# right.net
KiCad netlist of a schematic drawn in Altium Designer
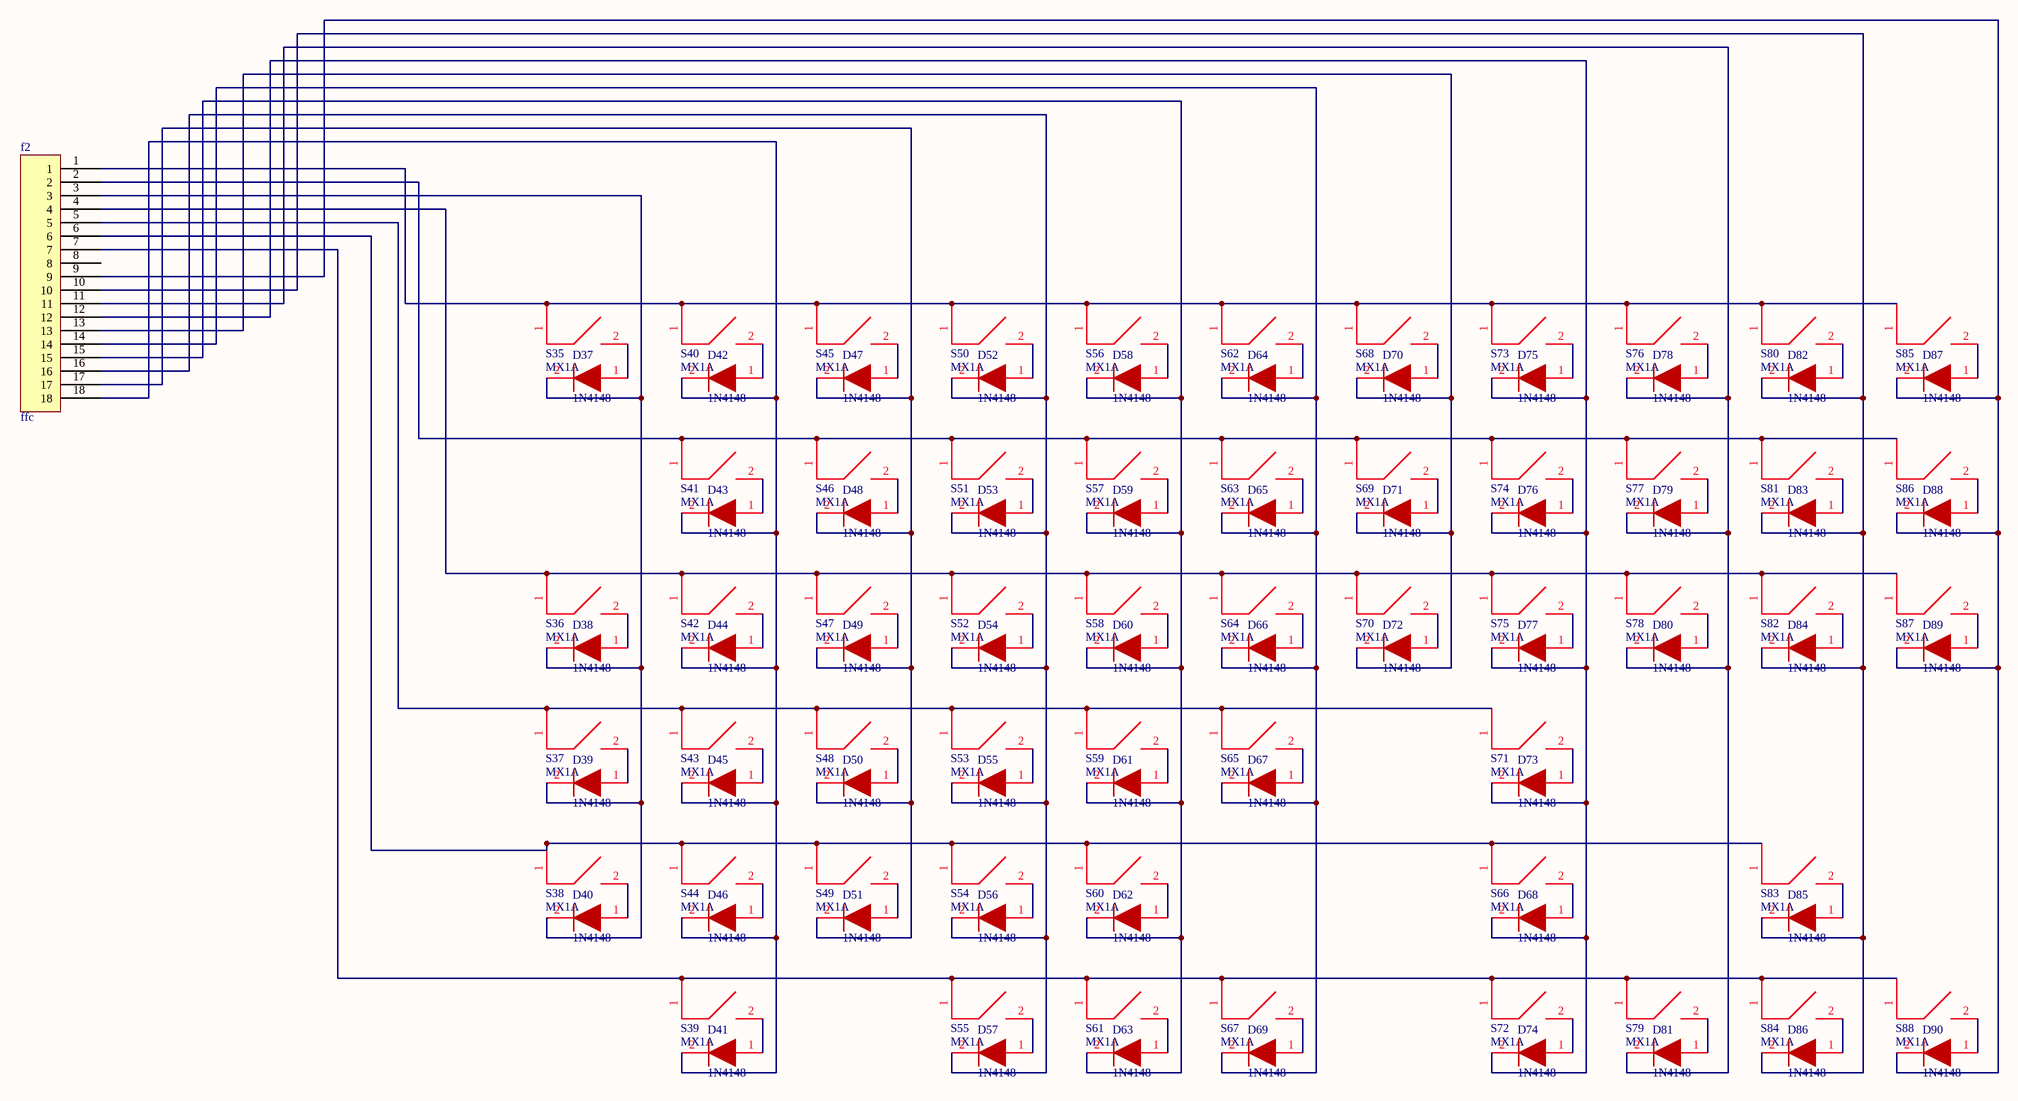
[diagram p0: right.SchDoc]

(export (version "E")
  (design (tool "Eeschema 10.0.6"))
  (components
    (comp (ref "D37")
      (value "1N4148")
      (footprint "SOD323")
      (description "二极管")
      (libsource (lib "keyboard") (part "1N4148"))
    )
    (comp (ref "D38")
      (value "1N4148")
      (footprint "SOD323")
      (description "二极管")
      (libsource (lib "keyboard") (part "1N4148"))
    )
    (comp (ref "D39")
      (value "1N4148")
      (footprint "SOD323")
      (description "二极管")
      (libsource (lib "keyboard") (part "1N4148"))
    )
    (comp (ref "D40")
      (value "1N4148")
      (footprint "SOD323")
      (description "二极管")
      (libsource (lib "keyboard") (part "1N4148"))
    )
    (comp (ref "D41")
      (value "1N4148")
      (footprint "SOD323")
      (description "二极管")
      (libsource (lib "keyboard") (part "1N4148"))
    )
    (comp (ref "D42")
      (value "1N4148")
      (footprint "SOD323")
      (description "二极管")
      (libsource (lib "keyboard") (part "1N4148"))
    )
    (comp (ref "D43")
      (value "1N4148")
      (footprint "SOD323")
      (description "二极管")
      (libsource (lib "keyboard") (part "1N4148"))
    )
    (comp (ref "D44")
      (value "1N4148")
      (footprint "SOD323")
      (description "二极管")
      (libsource (lib "keyboard") (part "1N4148"))
    )
    (comp (ref "D45")
      (value "1N4148")
      (footprint "SOD323")
      (description "二极管")
      (libsource (lib "keyboard") (part "1N4148"))
    )
    (comp (ref "D46")
      (value "1N4148")
      (footprint "SOD323")
      (description "二极管")
      (libsource (lib "keyboard") (part "1N4148"))
    )
    (comp (ref "D47")
      (value "1N4148")
      (footprint "SOD323")
      (description "二极管")
      (libsource (lib "keyboard") (part "1N4148"))
    )
    (comp (ref "D48")
      (value "1N4148")
      (footprint "SOD323")
      (description "二极管")
      (libsource (lib "keyboard") (part "1N4148"))
    )
    (comp (ref "D49")
      (value "1N4148")
      (footprint "SOD323")
      (description "二极管")
      (libsource (lib "keyboard") (part "1N4148"))
    )
    (comp (ref "D50")
      (value "1N4148")
      (footprint "SOD323")
      (description "二极管")
      (libsource (lib "keyboard") (part "1N4148"))
    )
    (comp (ref "D51")
      (value "1N4148")
      (footprint "SOD323")
      (description "二极管")
      (libsource (lib "keyboard") (part "1N4148"))
    )
    (comp (ref "D52")
      (value "1N4148")
      (footprint "SOD323")
      (description "二极管")
      (libsource (lib "keyboard") (part "1N4148"))
    )
    (comp (ref "D53")
      (value "1N4148")
      (footprint "SOD323")
      (description "二极管")
      (libsource (lib "keyboard") (part "1N4148"))
    )
    (comp (ref "D54")
      (value "1N4148")
      (footprint "SOD323")
      (description "二极管")
      (libsource (lib "keyboard") (part "1N4148"))
    )
    (comp (ref "D55")
      (value "1N4148")
      (footprint "SOD323")
      (description "二极管")
      (libsource (lib "keyboard") (part "1N4148"))
    )
    (comp (ref "D56")
      (value "1N4148")
      (footprint "SOD323")
      (description "二极管")
      (libsource (lib "keyboard") (part "1N4148"))
    )
    (comp (ref "D57")
      (value "1N4148")
      (footprint "SOD323")
      (description "二极管")
      (libsource (lib "keyboard") (part "1N4148"))
    )
    (comp (ref "D58")
      (value "1N4148")
      (footprint "SOD323")
      (description "二极管")
      (libsource (lib "keyboard") (part "1N4148"))
    )
    (comp (ref "D59")
      (value "1N4148")
      (footprint "SOD323")
      (description "二极管")
      (libsource (lib "keyboard") (part "1N4148"))
    )
    (comp (ref "D60")
      (value "1N4148")
      (footprint "SOD323")
      (description "二极管")
      (libsource (lib "keyboard") (part "1N4148"))
    )
    (comp (ref "D61")
      (value "1N4148")
      (footprint "SOD323")
      (description "二极管")
      (libsource (lib "keyboard") (part "1N4148"))
    )
    (comp (ref "D62")
      (value "1N4148")
      (footprint "SOD323")
      (description "二极管")
      (libsource (lib "keyboard") (part "1N4148"))
    )
    (comp (ref "D63")
      (value "1N4148")
      (footprint "SOD323")
      (description "二极管")
      (libsource (lib "keyboard") (part "1N4148"))
    )
    (comp (ref "D64")
      (value "1N4148")
      (footprint "SOD323")
      (description "二极管")
      (libsource (lib "keyboard") (part "1N4148"))
    )
    (comp (ref "D65")
      (value "1N4148")
      (footprint "SOD323")
      (description "二极管")
      (libsource (lib "keyboard") (part "1N4148"))
    )
    (comp (ref "D66")
      (value "1N4148")
      (footprint "SOD323")
      (description "二极管")
      (libsource (lib "keyboard") (part "1N4148"))
    )
    (comp (ref "D67")
      (value "1N4148")
      (footprint "SOD323")
      (description "二极管")
      (libsource (lib "keyboard") (part "1N4148"))
    )
    (comp (ref "D68")
      (value "1N4148")
      (footprint "SOD323")
      (description "二极管")
      (libsource (lib "keyboard") (part "1N4148"))
    )
    (comp (ref "D69")
      (value "1N4148")
      (footprint "SOD323")
      (description "二极管")
      (libsource (lib "keyboard") (part "1N4148"))
    )
    (comp (ref "D70")
      (value "1N4148")
      (footprint "SOD323")
      (description "二极管")
      (libsource (lib "keyboard") (part "1N4148"))
    )
    (comp (ref "D71")
      (value "1N4148")
      (footprint "SOD323")
      (description "二极管")
      (libsource (lib "keyboard") (part "1N4148"))
    )
    (comp (ref "D72")
      (value "1N4148")
      (footprint "SOD323")
      (description "二极管")
      (libsource (lib "keyboard") (part "1N4148"))
    )
    (comp (ref "D73")
      (value "1N4148")
      (footprint "SOD323")
      (description "二极管")
      (libsource (lib "keyboard") (part "1N4148"))
    )
    (comp (ref "D74")
      (value "1N4148")
      (footprint "SOD323")
      (description "二极管")
      (libsource (lib "keyboard") (part "1N4148"))
    )
    (comp (ref "D75")
      (value "1N4148")
      (footprint "SOD323")
      (description "二极管")
      (libsource (lib "keyboard") (part "1N4148"))
    )
    (comp (ref "D76")
      (value "1N4148")
      (footprint "SOD323")
      (description "二极管")
      (libsource (lib "keyboard") (part "1N4148"))
    )
    (comp (ref "D77")
      (value "1N4148")
      (footprint "SOD323")
      (description "二极管")
      (libsource (lib "keyboard") (part "1N4148"))
    )
    (comp (ref "D78")
      (value "1N4148")
      (footprint "SOD323")
      (description "二极管")
      (libsource (lib "keyboard") (part "1N4148"))
    )
    (comp (ref "D79")
      (value "1N4148")
      (footprint "SOD323")
      (description "二极管")
      (libsource (lib "keyboard") (part "1N4148"))
    )
    (comp (ref "D80")
      (value "1N4148")
      (footprint "SOD323")
      (description "二极管")
      (libsource (lib "keyboard") (part "1N4148"))
    )
    (comp (ref "D81")
      (value "1N4148")
      (footprint "SOD323")
      (description "二极管")
      (libsource (lib "keyboard") (part "1N4148"))
    )
    (comp (ref "D82")
      (value "1N4148")
      (footprint "SOD323")
      (description "二极管")
      (libsource (lib "keyboard") (part "1N4148"))
    )
    (comp (ref "D83")
      (value "1N4148")
      (footprint "SOD323")
      (description "二极管")
      (libsource (lib "keyboard") (part "1N4148"))
    )
    (comp (ref "D84")
      (value "1N4148")
      (footprint "SOD323")
      (description "二极管")
      (libsource (lib "keyboard") (part "1N4148"))
    )
    (comp (ref "D85")
      (value "1N4148")
      (footprint "SOD323")
      (description "二极管")
      (libsource (lib "keyboard") (part "1N4148"))
    )
    (comp (ref "D86")
      (value "1N4148")
      (footprint "SOD323")
      (description "二极管")
      (libsource (lib "keyboard") (part "1N4148"))
    )
    (comp (ref "D87")
      (value "1N4148")
      (footprint "SOD323")
      (description "二极管")
      (libsource (lib "keyboard") (part "1N4148"))
    )
    (comp (ref "D88")
      (value "1N4148")
      (footprint "SOD323")
      (description "二极管")
      (libsource (lib "keyboard") (part "1N4148"))
    )
    (comp (ref "D89")
      (value "1N4148")
      (footprint "SOD323")
      (description "二极管")
      (libsource (lib "keyboard") (part "1N4148"))
    )
    (comp (ref "D90")
      (value "1N4148")
      (footprint "SOD323")
      (description "二极管")
      (libsource (lib "keyboard") (part "1N4148"))
    )
    (comp (ref "f2") (value "ffc") (footprint "FFC") (libsource (lib "keyboard") (part "ffc")))
    (comp (ref "S35")
      (value "MX1A")
      (footprint "KEY")
      (description "按键")
      (libsource (lib "keyboard") (part "MX1A"))
    )
    (comp (ref "S36")
      (value "MX1A")
      (footprint "KEY")
      (description "按键")
      (libsource (lib "keyboard") (part "MX1A"))
    )
    (comp (ref "S37")
      (value "MX1A")
      (footprint "KEY")
      (description "按键")
      (libsource (lib "keyboard") (part "MX1A"))
    )
    (comp (ref "S38")
      (value "MX1A")
      (footprint "KEY")
      (description "按键")
      (libsource (lib "keyboard") (part "MX1A"))
    )
    (comp (ref "S39")
      (value "MX1A")
      (footprint "KEY")
      (description "按键")
      (libsource (lib "keyboard") (part "MX1A"))
    )
    (comp (ref "S40")
      (value "MX1A")
      (footprint "KEY")
      (description "按键")
      (libsource (lib "keyboard") (part "MX1A"))
    )
    (comp (ref "S41")
      (value "MX1A")
      (footprint "KEY")
      (description "按键")
      (libsource (lib "keyboard") (part "MX1A"))
    )
    (comp (ref "S42")
      (value "MX1A")
      (footprint "KEY")
      (description "按键")
      (libsource (lib "keyboard") (part "MX1A"))
    )
    (comp (ref "S43")
      (value "MX1A")
      (footprint "KEY")
      (description "按键")
      (libsource (lib "keyboard") (part "MX1A"))
    )
    (comp (ref "S44")
      (value "MX1A")
      (footprint "KEY")
      (description "按键")
      (libsource (lib "keyboard") (part "MX1A"))
    )
    (comp (ref "S45")
      (value "MX1A")
      (footprint "KEY")
      (description "按键")
      (libsource (lib "keyboard") (part "MX1A"))
    )
    (comp (ref "S46")
      (value "MX1A")
      (footprint "KEY")
      (description "按键")
      (libsource (lib "keyboard") (part "MX1A"))
    )
    (comp (ref "S47")
      (value "MX1A")
      (footprint "KEY")
      (description "按键")
      (libsource (lib "keyboard") (part "MX1A"))
    )
    (comp (ref "S48")
      (value "MX1A")
      (footprint "KEY")
      (description "按键")
      (libsource (lib "keyboard") (part "MX1A"))
    )
    (comp (ref "S49")
      (value "MX1A")
      (footprint "KEY")
      (description "按键")
      (libsource (lib "keyboard") (part "MX1A"))
    )
    (comp (ref "S50")
      (value "MX1A")
      (footprint "KEY")
      (description "按键")
      (libsource (lib "keyboard") (part "MX1A"))
    )
    (comp (ref "S51")
      (value "MX1A")
      (footprint "KEY")
      (description "按键")
      (libsource (lib "keyboard") (part "MX1A"))
    )
    (comp (ref "S52")
      (value "MX1A")
      (footprint "KEY")
      (description "按键")
      (libsource (lib "keyboard") (part "MX1A"))
    )
    (comp (ref "S53")
      (value "MX1A")
      (footprint "KEY")
      (description "按键")
      (libsource (lib "keyboard") (part "MX1A"))
    )
    (comp (ref "S54")
      (value "MX1A")
      (footprint "KEY")
      (description "按键")
      (libsource (lib "keyboard") (part "MX1A"))
    )
    (comp (ref "S55")
      (value "MX1A")
      (footprint "KEY")
      (description "按键")
      (libsource (lib "keyboard") (part "MX1A"))
    )
    (comp (ref "S56")
      (value "MX1A")
      (footprint "KEY")
      (description "按键")
      (libsource (lib "keyboard") (part "MX1A"))
    )
    (comp (ref "S57")
      (value "MX1A")
      (footprint "KEY")
      (description "按键")
      (libsource (lib "keyboard") (part "MX1A"))
    )
    (comp (ref "S58")
      (value "MX1A")
      (footprint "KEY")
      (description "按键")
      (libsource (lib "keyboard") (part "MX1A"))
    )
    (comp (ref "S59")
      (value "MX1A")
      (footprint "KEY")
      (description "按键")
      (libsource (lib "keyboard") (part "MX1A"))
    )
    (comp (ref "S60")
      (value "MX1A")
      (footprint "KEY")
      (description "按键")
      (libsource (lib "keyboard") (part "MX1A"))
    )
    (comp (ref "S61")
      (value "MX1A")
      (footprint "KEY")
      (description "按键")
      (libsource (lib "keyboard") (part "MX1A"))
    )
    (comp (ref "S62")
      (value "MX1A")
      (footprint "KEY")
      (description "按键")
      (libsource (lib "keyboard") (part "MX1A"))
    )
    (comp (ref "S63")
      (value "MX1A")
      (footprint "KEY")
      (description "按键")
      (libsource (lib "keyboard") (part "MX1A"))
    )
    (comp (ref "S64")
      (value "MX1A")
      (footprint "KEY")
      (description "按键")
      (libsource (lib "keyboard") (part "MX1A"))
    )
    (comp (ref "S65")
      (value "MX1A")
      (footprint "KEY")
      (description "按键")
      (libsource (lib "keyboard") (part "MX1A"))
    )
    (comp (ref "S66")
      (value "MX1A")
      (footprint "KEY")
      (description "按键")
      (libsource (lib "keyboard") (part "MX1A"))
    )
    (comp (ref "S67")
      (value "MX1A")
      (footprint "KEY")
      (description "按键")
      (libsource (lib "keyboard") (part "MX1A"))
    )
    (comp (ref "S68")
      (value "MX1A")
      (footprint "KEY")
      (description "按键")
      (libsource (lib "keyboard") (part "MX1A"))
    )
    (comp (ref "S69")
      (value "MX1A")
      (footprint "KEY")
      (description "按键")
      (libsource (lib "keyboard") (part "MX1A"))
    )
    (comp (ref "S70")
      (value "MX1A")
      (footprint "KEY")
      (description "按键")
      (libsource (lib "keyboard") (part "MX1A"))
    )
    (comp (ref "S71")
      (value "MX1A")
      (footprint "KEY")
      (description "按键")
      (libsource (lib "keyboard") (part "MX1A"))
    )
    (comp (ref "S72")
      (value "MX1A")
      (footprint "KEY")
      (description "按键")
      (libsource (lib "keyboard") (part "MX1A"))
    )
    (comp (ref "S73")
      (value "MX1A")
      (footprint "KEY")
      (description "按键")
      (libsource (lib "keyboard") (part "MX1A"))
    )
    (comp (ref "S74")
      (value "MX1A")
      (footprint "KEY")
      (description "按键")
      (libsource (lib "keyboard") (part "MX1A"))
    )
    (comp (ref "S75")
      (value "MX1A")
      (footprint "KEY")
      (description "按键")
      (libsource (lib "keyboard") (part "MX1A"))
    )
    (comp (ref "S76")
      (value "MX1A")
      (footprint "KEY")
      (description "按键")
      (libsource (lib "keyboard") (part "MX1A"))
    )
    (comp (ref "S77")
      (value "MX1A")
      (footprint "KEY")
      (description "按键")
      (libsource (lib "keyboard") (part "MX1A"))
    )
    (comp (ref "S78")
      (value "MX1A")
      (footprint "KEY")
      (description "按键")
      (libsource (lib "keyboard") (part "MX1A"))
    )
    (comp (ref "S79")
      (value "MX1A")
      (footprint "KEY")
      (description "按键")
      (libsource (lib "keyboard") (part "MX1A"))
    )
    (comp (ref "S80")
      (value "MX1A")
      (footprint "KEY")
      (description "按键")
      (libsource (lib "keyboard") (part "MX1A"))
    )
    (comp (ref "S81")
      (value "MX1A")
      (footprint "KEY")
      (description "按键")
      (libsource (lib "keyboard") (part "MX1A"))
    )
    (comp (ref "S82")
      (value "MX1A")
      (footprint "KEY")
      (description "按键")
      (libsource (lib "keyboard") (part "MX1A"))
    )
    (comp (ref "S83")
      (value "MX1A")
      (footprint "KEY")
      (description "按键")
      (libsource (lib "keyboard") (part "MX1A"))
    )
    (comp (ref "S84")
      (value "MX1A")
      (footprint "KEY")
      (description "按键")
      (libsource (lib "keyboard") (part "MX1A"))
    )
    (comp (ref "S85")
      (value "MX1A")
      (footprint "KEY")
      (description "按键")
      (libsource (lib "keyboard") (part "MX1A"))
    )
    (comp (ref "S86")
      (value "MX1A")
      (footprint "KEY")
      (description "按键")
      (libsource (lib "keyboard") (part "MX1A"))
    )
    (comp (ref "S87")
      (value "MX1A")
      (footprint "KEY")
      (description "按键")
      (libsource (lib "keyboard") (part "MX1A"))
    )
    (comp (ref "S88")
      (value "MX1A")
      (footprint "KEY")
      (description "按键")
      (libsource (lib "keyboard") (part "MX1A"))
    )
  )
  (nets
    (net (code "1") (name "Net-(D37-Pad1)") (class "Default")
      (node (ref "D37") (pin "1") (pinfunction "1_1") (pintype "passive"))
      (node (ref "S35") (pin "2") (pinfunction "2_2") (pintype "passive"))
    )
    (net (code "2") (name "Net-(D37-Pad2)") (class "Default")
      (node (ref "D37") (pin "2") (pinfunction "2_2") (pintype "passive"))
      (node (ref "D38") (pin "2") (pinfunction "2_2") (pintype "passive"))
      (node (ref "D39") (pin "2") (pinfunction "2_2") (pintype "passive"))
      (node (ref "D40") (pin "2") (pinfunction "2_2") (pintype "passive"))
      (node (ref "f2") (pin "3") (pinfunction "3_3") (pintype "passive"))
    )
    (net (code "3") (name "Net-(D38-Pad1)") (class "Default")
      (node (ref "D38") (pin "1") (pinfunction "1_1") (pintype "passive"))
      (node (ref "S36") (pin "2") (pinfunction "2_2") (pintype "passive"))
    )
    (net (code "4") (name "Net-(D39-Pad1)") (class "Default")
      (node (ref "D39") (pin "1") (pinfunction "1_1") (pintype "passive"))
      (node (ref "S37") (pin "2") (pinfunction "2_2") (pintype "passive"))
    )
    (net (code "5") (name "Net-(D40-Pad1)") (class "Default")
      (node (ref "D40") (pin "1") (pinfunction "1_1") (pintype "passive"))
      (node (ref "S38") (pin "2") (pinfunction "2_2") (pintype "passive"))
    )
    (net (code "6") (name "Net-(D41-Pad1)") (class "Default")
      (node (ref "D41") (pin "1") (pinfunction "1_1") (pintype "passive"))
      (node (ref "S39") (pin "2") (pinfunction "2_2") (pintype "passive"))
    )
    (net (code "7") (name "Net-(D41-Pad2)") (class "Default")
      (node (ref "D41") (pin "2") (pinfunction "2_2") (pintype "passive"))
      (node (ref "D42") (pin "2") (pinfunction "2_2") (pintype "passive"))
      (node (ref "D43") (pin "2") (pinfunction "2_2") (pintype "passive"))
      (node (ref "D44") (pin "2") (pinfunction "2_2") (pintype "passive"))
      (node (ref "D45") (pin "2") (pinfunction "2_2") (pintype "passive"))
      (node (ref "D46") (pin "2") (pinfunction "2_2") (pintype "passive"))
      (node (ref "f2") (pin "18") (pinfunction "18_18") (pintype "passive"))
    )
    (net (code "8") (name "Net-(D42-Pad1)") (class "Default")
      (node (ref "D42") (pin "1") (pinfunction "1_1") (pintype "passive"))
      (node (ref "S40") (pin "2") (pinfunction "2_2") (pintype "passive"))
    )
    (net (code "9") (name "Net-(D43-Pad1)") (class "Default")
      (node (ref "D43") (pin "1") (pinfunction "1_1") (pintype "passive"))
      (node (ref "S41") (pin "2") (pinfunction "2_2") (pintype "passive"))
    )
    (net (code "10") (name "Net-(D44-Pad1)") (class "Default")
      (node (ref "D44") (pin "1") (pinfunction "1_1") (pintype "passive"))
      (node (ref "S42") (pin "2") (pinfunction "2_2") (pintype "passive"))
    )
    (net (code "11") (name "Net-(D45-Pad1)") (class "Default")
      (node (ref "D45") (pin "1") (pinfunction "1_1") (pintype "passive"))
      (node (ref "S43") (pin "2") (pinfunction "2_2") (pintype "passive"))
    )
    (net (code "12") (name "Net-(D46-Pad1)") (class "Default")
      (node (ref "D46") (pin "1") (pinfunction "1_1") (pintype "passive"))
      (node (ref "S44") (pin "2") (pinfunction "2_2") (pintype "passive"))
    )
    (net (code "13") (name "Net-(D47-Pad1)") (class "Default")
      (node (ref "D47") (pin "1") (pinfunction "1_1") (pintype "passive"))
      (node (ref "S45") (pin "2") (pinfunction "2_2") (pintype "passive"))
    )
    (net (code "14") (name "Net-(D47-Pad2)") (class "Default")
      (node (ref "D47") (pin "2") (pinfunction "2_2") (pintype "passive"))
      (node (ref "D48") (pin "2") (pinfunction "2_2") (pintype "passive"))
      (node (ref "D49") (pin "2") (pinfunction "2_2") (pintype "passive"))
      (node (ref "D50") (pin "2") (pinfunction "2_2") (pintype "passive"))
      (node (ref "D51") (pin "2") (pinfunction "2_2") (pintype "passive"))
      (node (ref "f2") (pin "17") (pinfunction "17_17") (pintype "passive"))
    )
    (net (code "15") (name "Net-(D48-Pad1)") (class "Default")
      (node (ref "D48") (pin "1") (pinfunction "1_1") (pintype "passive"))
      (node (ref "S46") (pin "2") (pinfunction "2_2") (pintype "passive"))
    )
    (net (code "16") (name "Net-(D49-Pad1)") (class "Default")
      (node (ref "D49") (pin "1") (pinfunction "1_1") (pintype "passive"))
      (node (ref "S47") (pin "2") (pinfunction "2_2") (pintype "passive"))
    )
    (net (code "17") (name "Net-(D50-Pad1)") (class "Default")
      (node (ref "D50") (pin "1") (pinfunction "1_1") (pintype "passive"))
      (node (ref "S48") (pin "2") (pinfunction "2_2") (pintype "passive"))
    )
    (net (code "18") (name "Net-(D51-Pad1)") (class "Default")
      (node (ref "D51") (pin "1") (pinfunction "1_1") (pintype "passive"))
      (node (ref "S49") (pin "2") (pinfunction "2_2") (pintype "passive"))
    )
    (net (code "19") (name "Net-(D52-Pad1)") (class "Default")
      (node (ref "D52") (pin "1") (pinfunction "1_1") (pintype "passive"))
      (node (ref "S50") (pin "2") (pinfunction "2_2") (pintype "passive"))
    )
    (net (code "20") (name "Net-(D52-Pad2)") (class "Default")
      (node (ref "D52") (pin "2") (pinfunction "2_2") (pintype "passive"))
      (node (ref "D53") (pin "2") (pinfunction "2_2") (pintype "passive"))
      (node (ref "D54") (pin "2") (pinfunction "2_2") (pintype "passive"))
      (node (ref "D55") (pin "2") (pinfunction "2_2") (pintype "passive"))
      (node (ref "D56") (pin "2") (pinfunction "2_2") (pintype "passive"))
      (node (ref "D57") (pin "2") (pinfunction "2_2") (pintype "passive"))
      (node (ref "f2") (pin "16") (pinfunction "16_16") (pintype "passive"))
    )
    (net (code "21") (name "Net-(D53-Pad1)") (class "Default")
      (node (ref "D53") (pin "1") (pinfunction "1_1") (pintype "passive"))
      (node (ref "S51") (pin "2") (pinfunction "2_2") (pintype "passive"))
    )
    (net (code "22") (name "Net-(D54-Pad1)") (class "Default")
      (node (ref "D54") (pin "1") (pinfunction "1_1") (pintype "passive"))
      (node (ref "S52") (pin "2") (pinfunction "2_2") (pintype "passive"))
    )
    (net (code "23") (name "Net-(D55-Pad1)") (class "Default")
      (node (ref "D55") (pin "1") (pinfunction "1_1") (pintype "passive"))
      (node (ref "S53") (pin "2") (pinfunction "2_2") (pintype "passive"))
    )
    (net (code "24") (name "Net-(D56-Pad1)") (class "Default")
      (node (ref "D56") (pin "1") (pinfunction "1_1") (pintype "passive"))
      (node (ref "S54") (pin "2") (pinfunction "2_2") (pintype "passive"))
    )
    (net (code "25") (name "Net-(D57-Pad1)") (class "Default")
      (node (ref "D57") (pin "1") (pinfunction "1_1") (pintype "passive"))
      (node (ref "S55") (pin "2") (pinfunction "2_2") (pintype "passive"))
    )
    (net (code "26") (name "Net-(D58-Pad1)") (class "Default")
      (node (ref "D58") (pin "1") (pinfunction "1_1") (pintype "passive"))
      (node (ref "S56") (pin "2") (pinfunction "2_2") (pintype "passive"))
    )
    (net (code "27") (name "Net-(D58-Pad2)") (class "Default")
      (node (ref "D58") (pin "2") (pinfunction "2_2") (pintype "passive"))
      (node (ref "D59") (pin "2") (pinfunction "2_2") (pintype "passive"))
      (node (ref "D60") (pin "2") (pinfunction "2_2") (pintype "passive"))
      (node (ref "D61") (pin "2") (pinfunction "2_2") (pintype "passive"))
      (node (ref "D62") (pin "2") (pinfunction "2_2") (pintype "passive"))
      (node (ref "D63") (pin "2") (pinfunction "2_2") (pintype "passive"))
      (node (ref "f2") (pin "15") (pinfunction "15_15") (pintype "passive"))
    )
    (net (code "28") (name "Net-(D59-Pad1)") (class "Default")
      (node (ref "D59") (pin "1") (pinfunction "1_1") (pintype "passive"))
      (node (ref "S57") (pin "2") (pinfunction "2_2") (pintype "passive"))
    )
    (net (code "29") (name "Net-(D60-Pad1)") (class "Default")
      (node (ref "D60") (pin "1") (pinfunction "1_1") (pintype "passive"))
      (node (ref "S58") (pin "2") (pinfunction "2_2") (pintype "passive"))
    )
    (net (code "30") (name "Net-(D61-Pad1)") (class "Default")
      (node (ref "D61") (pin "1") (pinfunction "1_1") (pintype "passive"))
      (node (ref "S59") (pin "2") (pinfunction "2_2") (pintype "passive"))
    )
    (net (code "31") (name "Net-(D62-Pad1)") (class "Default")
      (node (ref "D62") (pin "1") (pinfunction "1_1") (pintype "passive"))
      (node (ref "S60") (pin "2") (pinfunction "2_2") (pintype "passive"))
    )
    (net (code "32") (name "Net-(D63-Pad1)") (class "Default")
      (node (ref "D63") (pin "1") (pinfunction "1_1") (pintype "passive"))
      (node (ref "S61") (pin "2") (pinfunction "2_2") (pintype "passive"))
    )
    (net (code "33") (name "Net-(D64-Pad1)") (class "Default")
      (node (ref "D64") (pin "1") (pinfunction "1_1") (pintype "passive"))
      (node (ref "S62") (pin "2") (pinfunction "2_2") (pintype "passive"))
    )
    (net (code "34") (name "Net-(D64-Pad2)") (class "Default")
      (node (ref "D64") (pin "2") (pinfunction "2_2") (pintype "passive"))
      (node (ref "D65") (pin "2") (pinfunction "2_2") (pintype "passive"))
      (node (ref "D66") (pin "2") (pinfunction "2_2") (pintype "passive"))
      (node (ref "D67") (pin "2") (pinfunction "2_2") (pintype "passive"))
      (node (ref "D69") (pin "2") (pinfunction "2_2") (pintype "passive"))
      (node (ref "f2") (pin "14") (pinfunction "14_14") (pintype "passive"))
    )
    (net (code "35") (name "Net-(D65-Pad1)") (class "Default")
      (node (ref "D65") (pin "1") (pinfunction "1_1") (pintype "passive"))
      (node (ref "S63") (pin "2") (pinfunction "2_2") (pintype "passive"))
    )
    (net (code "36") (name "Net-(D66-Pad1)") (class "Default")
      (node (ref "D66") (pin "1") (pinfunction "1_1") (pintype "passive"))
      (node (ref "S64") (pin "2") (pinfunction "2_2") (pintype "passive"))
    )
    (net (code "37") (name "Net-(D67-Pad1)") (class "Default")
      (node (ref "D67") (pin "1") (pinfunction "1_1") (pintype "passive"))
      (node (ref "S65") (pin "2") (pinfunction "2_2") (pintype "passive"))
    )
    (net (code "38") (name "Net-(D68-Pad1)") (class "Default")
      (node (ref "D68") (pin "1") (pinfunction "1_1") (pintype "passive"))
      (node (ref "S66") (pin "2") (pinfunction "2_2") (pintype "passive"))
    )
    (net (code "39") (name "Net-(D68-Pad2)") (class "Default")
      (node (ref "D68") (pin "2") (pinfunction "2_2") (pintype "passive"))
      (node (ref "D73") (pin "2") (pinfunction "2_2") (pintype "passive"))
      (node (ref "D74") (pin "2") (pinfunction "2_2") (pintype "passive"))
      (node (ref "D75") (pin "2") (pinfunction "2_2") (pintype "passive"))
      (node (ref "D76") (pin "2") (pinfunction "2_2") (pintype "passive"))
      (node (ref "D77") (pin "2") (pinfunction "2_2") (pintype "passive"))
      (node (ref "f2") (pin "12") (pinfunction "12_12") (pintype "passive"))
    )
    (net (code "40") (name "Net-(D69-Pad1)") (class "Default")
      (node (ref "D69") (pin "1") (pinfunction "1_1") (pintype "passive"))
      (node (ref "S67") (pin "2") (pinfunction "2_2") (pintype "passive"))
    )
    (net (code "41") (name "Net-(D70-Pad1)") (class "Default")
      (node (ref "D70") (pin "1") (pinfunction "1_1") (pintype "passive"))
      (node (ref "S68") (pin "2") (pinfunction "2_2") (pintype "passive"))
    )
    (net (code "42") (name "Net-(D70-Pad2)") (class "Default")
      (node (ref "D70") (pin "2") (pinfunction "2_2") (pintype "passive"))
      (node (ref "D71") (pin "2") (pinfunction "2_2") (pintype "passive"))
      (node (ref "D72") (pin "2") (pinfunction "2_2") (pintype "passive"))
      (node (ref "f2") (pin "13") (pinfunction "13_13") (pintype "passive"))
    )
    (net (code "43") (name "Net-(D71-Pad1)") (class "Default")
      (node (ref "D71") (pin "1") (pinfunction "1_1") (pintype "passive"))
      (node (ref "S69") (pin "2") (pinfunction "2_2") (pintype "passive"))
    )
    (net (code "44") (name "Net-(D72-Pad1)") (class "Default")
      (node (ref "D72") (pin "1") (pinfunction "1_1") (pintype "passive"))
      (node (ref "S70") (pin "2") (pinfunction "2_2") (pintype "passive"))
    )
    (net (code "45") (name "Net-(D73-Pad1)") (class "Default")
      (node (ref "D73") (pin "1") (pinfunction "1_1") (pintype "passive"))
      (node (ref "S71") (pin "2") (pinfunction "2_2") (pintype "passive"))
    )
    (net (code "46") (name "Net-(D74-Pad1)") (class "Default")
      (node (ref "D74") (pin "1") (pinfunction "1_1") (pintype "passive"))
      (node (ref "S72") (pin "2") (pinfunction "2_2") (pintype "passive"))
    )
    (net (code "47") (name "Net-(D75-Pad1)") (class "Default")
      (node (ref "D75") (pin "1") (pinfunction "1_1") (pintype "passive"))
      (node (ref "S73") (pin "2") (pinfunction "2_2") (pintype "passive"))
    )
    (net (code "48") (name "Net-(D76-Pad1)") (class "Default")
      (node (ref "D76") (pin "1") (pinfunction "1_1") (pintype "passive"))
      (node (ref "S74") (pin "2") (pinfunction "2_2") (pintype "passive"))
    )
    (net (code "49") (name "Net-(D77-Pad1)") (class "Default")
      (node (ref "D77") (pin "1") (pinfunction "1_1") (pintype "passive"))
      (node (ref "S75") (pin "2") (pinfunction "2_2") (pintype "passive"))
    )
    (net (code "50") (name "Net-(D78-Pad1)") (class "Default")
      (node (ref "D78") (pin "1") (pinfunction "1_1") (pintype "passive"))
      (node (ref "S76") (pin "2") (pinfunction "2_2") (pintype "passive"))
    )
    (net (code "51") (name "Net-(D78-Pad2)") (class "Default")
      (node (ref "D78") (pin "2") (pinfunction "2_2") (pintype "passive"))
      (node (ref "D79") (pin "2") (pinfunction "2_2") (pintype "passive"))
      (node (ref "D80") (pin "2") (pinfunction "2_2") (pintype "passive"))
      (node (ref "D81") (pin "2") (pinfunction "2_2") (pintype "passive"))
      (node (ref "f2") (pin "11") (pinfunction "11_11") (pintype "passive"))
    )
    (net (code "52") (name "Net-(D79-Pad1)") (class "Default")
      (node (ref "D79") (pin "1") (pinfunction "1_1") (pintype "passive"))
      (node (ref "S77") (pin "2") (pinfunction "2_2") (pintype "passive"))
    )
    (net (code "53") (name "Net-(D80-Pad1)") (class "Default")
      (node (ref "D80") (pin "1") (pinfunction "1_1") (pintype "passive"))
      (node (ref "S78") (pin "2") (pinfunction "2_2") (pintype "passive"))
    )
    (net (code "54") (name "Net-(D81-Pad1)") (class "Default")
      (node (ref "D81") (pin "1") (pinfunction "1_1") (pintype "passive"))
      (node (ref "S79") (pin "2") (pinfunction "2_2") (pintype "passive"))
    )
    (net (code "55") (name "Net-(D82-Pad1)") (class "Default")
      (node (ref "D82") (pin "1") (pinfunction "1_1") (pintype "passive"))
      (node (ref "S80") (pin "2") (pinfunction "2_2") (pintype "passive"))
    )
    (net (code "56") (name "Net-(D82-Pad2)") (class "Default")
      (node (ref "D82") (pin "2") (pinfunction "2_2") (pintype "passive"))
      (node (ref "D83") (pin "2") (pinfunction "2_2") (pintype "passive"))
      (node (ref "D84") (pin "2") (pinfunction "2_2") (pintype "passive"))
      (node (ref "D85") (pin "2") (pinfunction "2_2") (pintype "passive"))
      (node (ref "D86") (pin "2") (pinfunction "2_2") (pintype "passive"))
      (node (ref "f2") (pin "10") (pinfunction "10_10") (pintype "passive"))
    )
    (net (code "57") (name "Net-(D83-Pad1)") (class "Default")
      (node (ref "D83") (pin "1") (pinfunction "1_1") (pintype "passive"))
      (node (ref "S81") (pin "2") (pinfunction "2_2") (pintype "passive"))
    )
    (net (code "58") (name "Net-(D84-Pad1)") (class "Default")
      (node (ref "D84") (pin "1") (pinfunction "1_1") (pintype "passive"))
      (node (ref "S82") (pin "2") (pinfunction "2_2") (pintype "passive"))
    )
    (net (code "59") (name "Net-(D85-Pad1)") (class "Default")
      (node (ref "D85") (pin "1") (pinfunction "1_1") (pintype "passive"))
      (node (ref "S83") (pin "2") (pinfunction "2_2") (pintype "passive"))
    )
    (net (code "60") (name "Net-(D86-Pad1)") (class "Default")
      (node (ref "D86") (pin "1") (pinfunction "1_1") (pintype "passive"))
      (node (ref "S84") (pin "2") (pinfunction "2_2") (pintype "passive"))
    )
    (net (code "61") (name "Net-(D87-Pad1)") (class "Default")
      (node (ref "D87") (pin "1") (pinfunction "1_1") (pintype "passive"))
      (node (ref "S85") (pin "2") (pinfunction "2_2") (pintype "passive"))
    )
    (net (code "62") (name "Net-(D87-Pad2)") (class "Default")
      (node (ref "D87") (pin "2") (pinfunction "2_2") (pintype "passive"))
      (node (ref "D88") (pin "2") (pinfunction "2_2") (pintype "passive"))
      (node (ref "D89") (pin "2") (pinfunction "2_2") (pintype "passive"))
      (node (ref "D90") (pin "2") (pinfunction "2_2") (pintype "passive"))
      (node (ref "f2") (pin "9") (pinfunction "9_9") (pintype "passive"))
    )
    (net (code "63") (name "Net-(D88-Pad1)") (class "Default")
      (node (ref "D88") (pin "1") (pinfunction "1_1") (pintype "passive"))
      (node (ref "S86") (pin "2") (pinfunction "2_2") (pintype "passive"))
    )
    (net (code "64") (name "Net-(D89-Pad1)") (class "Default")
      (node (ref "D89") (pin "1") (pinfunction "1_1") (pintype "passive"))
      (node (ref "S87") (pin "2") (pinfunction "2_2") (pintype "passive"))
    )
    (net (code "65") (name "Net-(D90-Pad1)") (class "Default")
      (node (ref "D90") (pin "1") (pinfunction "1_1") (pintype "passive"))
      (node (ref "S88") (pin "2") (pinfunction "2_2") (pintype "passive"))
    )
    (net (code "66") (name "Net-(S35-Pad1)") (class "Default")
      (node (ref "S35") (pin "1") (pinfunction "1_1") (pintype "passive"))
      (node (ref "S40") (pin "1") (pinfunction "1_1") (pintype "passive"))
      (node (ref "S45") (pin "1") (pinfunction "1_1") (pintype "passive"))
      (node (ref "S50") (pin "1") (pinfunction "1_1") (pintype "passive"))
      (node (ref "S56") (pin "1") (pinfunction "1_1") (pintype "passive"))
      (node (ref "S62") (pin "1") (pinfunction "1_1") (pintype "passive"))
      (node (ref "S68") (pin "1") (pinfunction "1_1") (pintype "passive"))
      (node (ref "S73") (pin "1") (pinfunction "1_1") (pintype "passive"))
      (node (ref "S76") (pin "1") (pinfunction "1_1") (pintype "passive"))
      (node (ref "S80") (pin "1") (pinfunction "1_1") (pintype "passive"))
      (node (ref "S85") (pin "1") (pinfunction "1_1") (pintype "passive"))
      (node (ref "f2") (pin "1") (pinfunction "1_1") (pintype "passive"))
    )
    (net (code "67") (name "Net-(S36-Pad1)") (class "Default")
      (node (ref "S36") (pin "1") (pinfunction "1_1") (pintype "passive"))
      (node (ref "S42") (pin "1") (pinfunction "1_1") (pintype "passive"))
      (node (ref "S47") (pin "1") (pinfunction "1_1") (pintype "passive"))
      (node (ref "S52") (pin "1") (pinfunction "1_1") (pintype "passive"))
      (node (ref "S58") (pin "1") (pinfunction "1_1") (pintype "passive"))
      (node (ref "S64") (pin "1") (pinfunction "1_1") (pintype "passive"))
      (node (ref "S70") (pin "1") (pinfunction "1_1") (pintype "passive"))
      (node (ref "S75") (pin "1") (pinfunction "1_1") (pintype "passive"))
      (node (ref "S78") (pin "1") (pinfunction "1_1") (pintype "passive"))
      (node (ref "S82") (pin "1") (pinfunction "1_1") (pintype "passive"))
      (node (ref "S87") (pin "1") (pinfunction "1_1") (pintype "passive"))
      (node (ref "f2") (pin "4") (pinfunction "4_4") (pintype "passive"))
    )
    (net (code "68") (name "Net-(S37-Pad1)") (class "Default")
      (node (ref "S37") (pin "1") (pinfunction "1_1") (pintype "passive"))
      (node (ref "S43") (pin "1") (pinfunction "1_1") (pintype "passive"))
      (node (ref "S48") (pin "1") (pinfunction "1_1") (pintype "passive"))
      (node (ref "S53") (pin "1") (pinfunction "1_1") (pintype "passive"))
      (node (ref "S59") (pin "1") (pinfunction "1_1") (pintype "passive"))
      (node (ref "S65") (pin "1") (pinfunction "1_1") (pintype "passive"))
      (node (ref "S71") (pin "1") (pinfunction "1_1") (pintype "passive"))
      (node (ref "f2") (pin "5") (pinfunction "5_5") (pintype "passive"))
    )
    (net (code "69") (name "Net-(S38-Pad1)") (class "Default")
      (node (ref "S38") (pin "1") (pinfunction "1_1") (pintype "passive"))
      (node (ref "S44") (pin "1") (pinfunction "1_1") (pintype "passive"))
      (node (ref "S49") (pin "1") (pinfunction "1_1") (pintype "passive"))
      (node (ref "S54") (pin "1") (pinfunction "1_1") (pintype "passive"))
      (node (ref "S60") (pin "1") (pinfunction "1_1") (pintype "passive"))
      (node (ref "S66") (pin "1") (pinfunction "1_1") (pintype "passive"))
      (node (ref "S83") (pin "1") (pinfunction "1_1") (pintype "passive"))
      (node (ref "f2") (pin "6") (pinfunction "6_6") (pintype "passive"))
    )
    (net (code "70") (name "Net-(S39-Pad1)") (class "Default")
      (node (ref "S39") (pin "1") (pinfunction "1_1") (pintype "passive"))
      (node (ref "S55") (pin "1") (pinfunction "1_1") (pintype "passive"))
      (node (ref "S61") (pin "1") (pinfunction "1_1") (pintype "passive"))
      (node (ref "S67") (pin "1") (pinfunction "1_1") (pintype "passive"))
      (node (ref "S72") (pin "1") (pinfunction "1_1") (pintype "passive"))
      (node (ref "S79") (pin "1") (pinfunction "1_1") (pintype "passive"))
      (node (ref "S84") (pin "1") (pinfunction "1_1") (pintype "passive"))
      (node (ref "S88") (pin "1") (pinfunction "1_1") (pintype "passive"))
      (node (ref "f2") (pin "7") (pinfunction "7_7") (pintype "passive"))
    )
    (net (code "71") (name "Net-(S41-Pad1)") (class "Default")
      (node (ref "S41") (pin "1") (pinfunction "1_1") (pintype "passive"))
      (node (ref "S46") (pin "1") (pinfunction "1_1") (pintype "passive"))
      (node (ref "S51") (pin "1") (pinfunction "1_1") (pintype "passive"))
      (node (ref "S57") (pin "1") (pinfunction "1_1") (pintype "passive"))
      (node (ref "S63") (pin "1") (pinfunction "1_1") (pintype "passive"))
      (node (ref "S69") (pin "1") (pinfunction "1_1") (pintype "passive"))
      (node (ref "S74") (pin "1") (pinfunction "1_1") (pintype "passive"))
      (node (ref "S77") (pin "1") (pinfunction "1_1") (pintype "passive"))
      (node (ref "S81") (pin "1") (pinfunction "1_1") (pintype "passive"))
      (node (ref "S86") (pin "1") (pinfunction "1_1") (pintype "passive"))
      (node (ref "f2") (pin "2") (pinfunction "2_2") (pintype "passive"))
    )
    (net (code "72") (name "unconnected-(f2-Pad8)") (class "Default")
      (node (ref "f2") (pin "8") (pinfunction "8_8") (pintype "passive"))
    )
  )
)
